# MFO.net
KiCad netlist of a schematic drawn in EAGLE
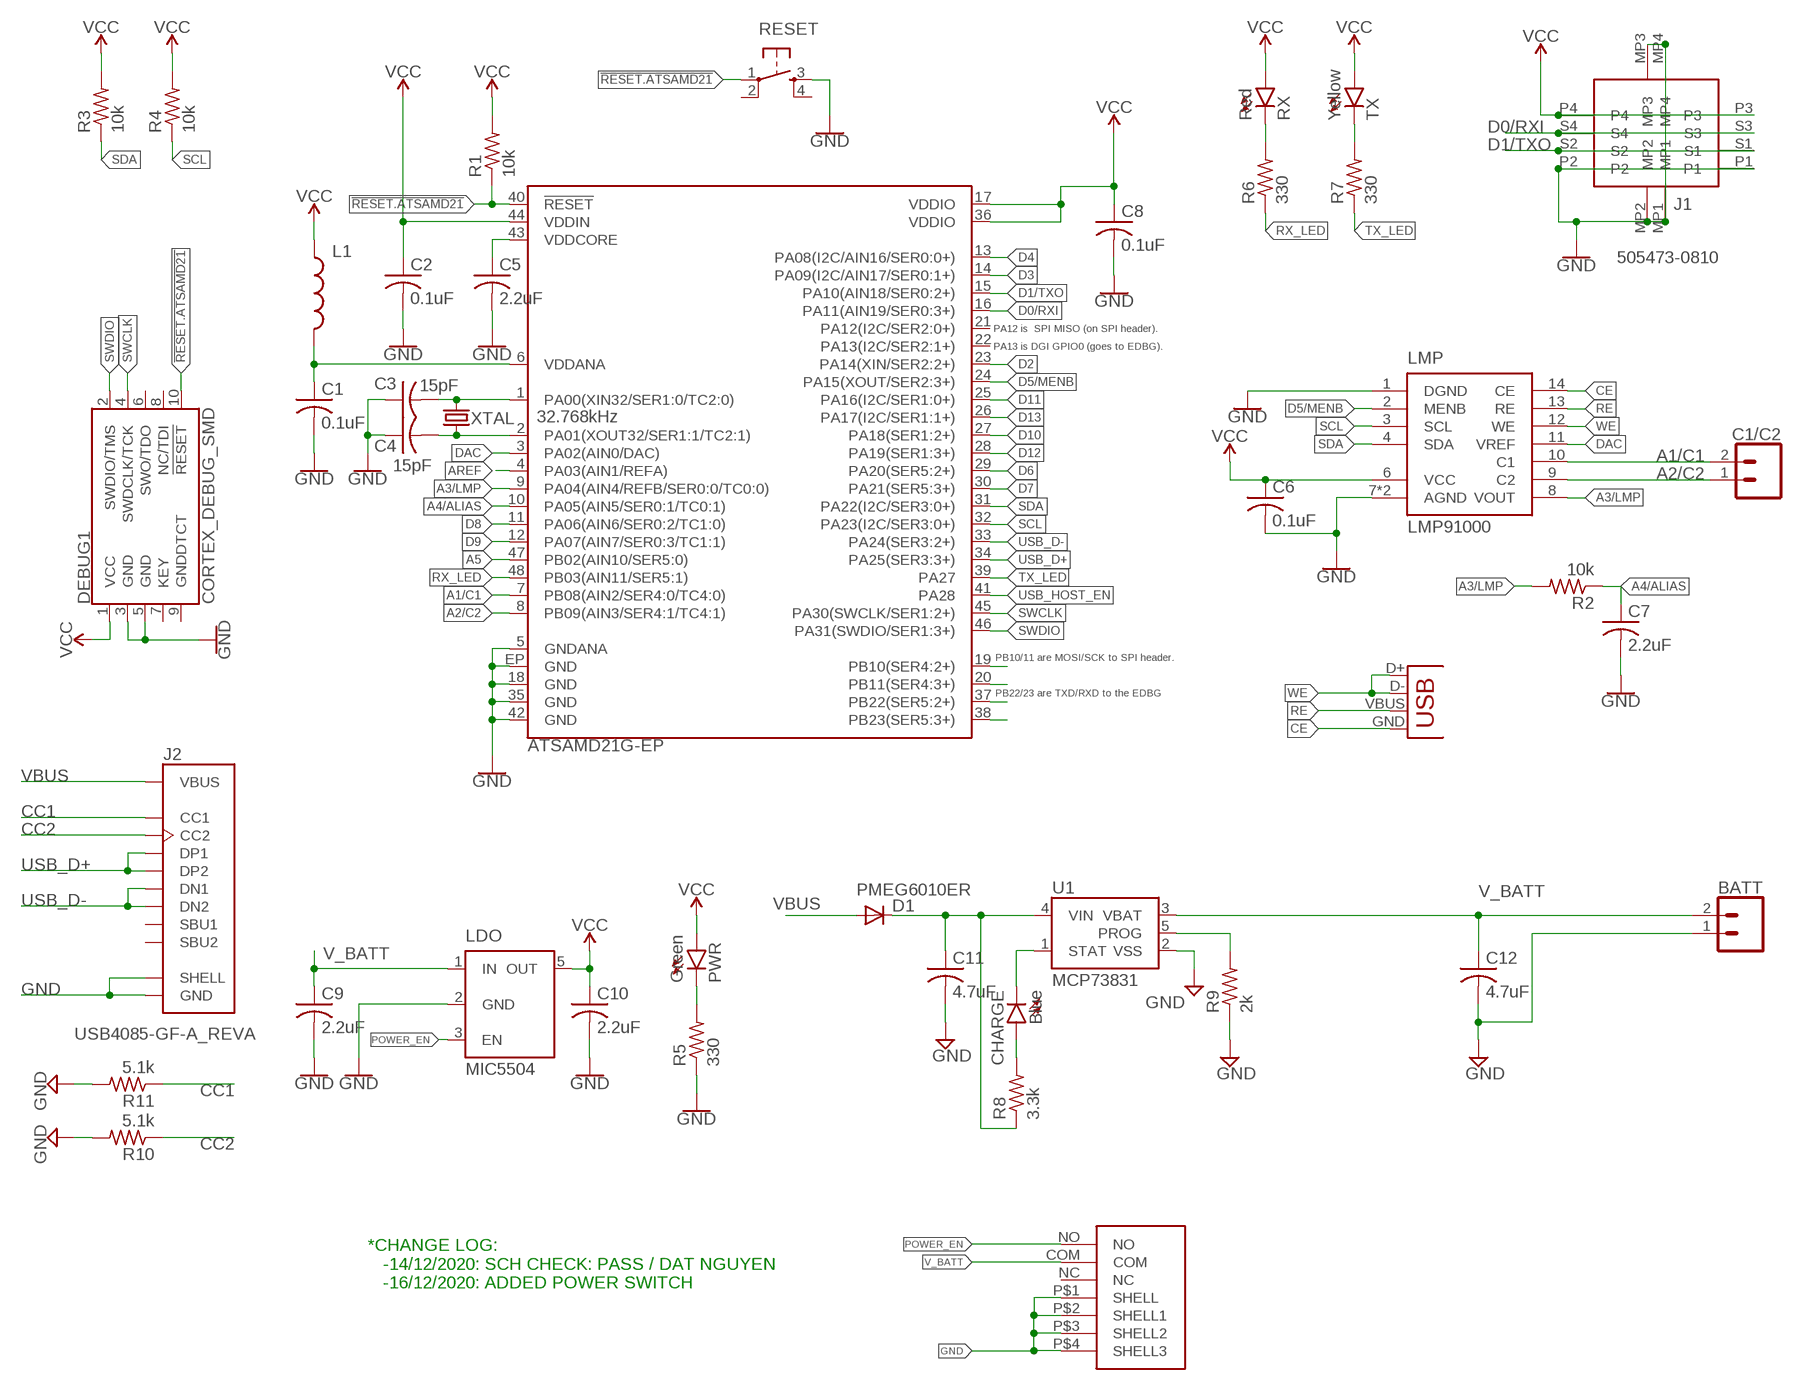
[diagram p0: schematic, sheet 1]

(export (version "E")
  (design (tool "Eeschema 10.0.6"))
  (components
    (comp (ref "ARDUINO")
      (value "ATSAMD21G-EP")
      (footprint "eagle-import:QFN-48")
      (libsource (lib "eagle-import") (part "ATSAMD21G-EP"))
    )
    (comp (ref "BATT")
      (value "CONN_02")
      (footprint "eagle-import:1X02")
      (libsource (lib "eagle-import") (part "CONN_02"))
    )
    (comp (ref "C1")
      (value "0.1uF")
      (footprint "eagle-import:C0603")
      (libsource (lib "eagle-import") (part "C-USC0603"))
    )
    (comp (ref "C1/C2")
      (value "CONN_02")
      (footprint "eagle-import:1X02")
      (libsource (lib "eagle-import") (part "CONN_02"))
    )
    (comp (ref "C2")
      (value "0.1uF")
      (footprint "eagle-import:C0603")
      (libsource (lib "eagle-import") (part "C-USC0603"))
    )
    (comp (ref "C3")
      (value "15pF")
      (footprint "eagle-import:C0603")
      (libsource (lib "eagle-import") (part "C-USC0603"))
    )
    (comp (ref "C4")
      (value "15pF")
      (footprint "eagle-import:C0603")
      (libsource (lib "eagle-import") (part "C-USC0603"))
    )
    (comp (ref "C5")
      (value "2.2uF")
      (footprint "eagle-import:C0603")
      (libsource (lib "eagle-import") (part "C-USC0603"))
    )
    (comp (ref "C6")
      (value "0.1uF")
      (footprint "eagle-import:C0603")
      (libsource (lib "eagle-import") (part "C-USC0603"))
    )
    (comp (ref "C7")
      (value "2.2uF")
      (footprint "eagle-import:C0603")
      (libsource (lib "eagle-import") (part "C-USC0603"))
    )
    (comp (ref "C8")
      (value "0.1uF")
      (footprint "eagle-import:C0603")
      (libsource (lib "eagle-import") (part "C-USC0603"))
    )
    (comp (ref "C9")
      (value "2.2uF")
      (footprint "eagle-import:C0603")
      (libsource (lib "eagle-import") (part "C-USC0603"))
    )
    (comp (ref "C10")
      (value "2.2uF")
      (footprint "eagle-import:C0603")
      (libsource (lib "eagle-import") (part "C-USC0603"))
    )
    (comp (ref "C11")
      (value "4.7uF")
      (footprint "eagle-import:C0603")
      (libsource (lib "eagle-import") (part "C-USC0603"))
    )
    (comp (ref "C12")
      (value "4.7uF")
      (footprint "eagle-import:C0603")
      (libsource (lib "eagle-import") (part "C-USC0603"))
    )
    (comp (ref "CHARGE")
      (value "Blue")
      (footprint "eagle-import:CHIP-LED0805")
      (libsource (lib "eagle-import") (part "LEDCHIP-LED0805"))
    )
    (comp (ref "D1")
      (value "PMEG6010ER")
      (footprint "eagle-import:DIODE_SOD123")
      (libsource (lib "eagle-import") (part "DIODE_DIODE-SOD123"))
    )
    (comp (ref "DEBUG1")
      (value "CORTEX_DEBUG_SMD")
      (footprint "eagle-import:SAMTECH_FTSH-105-01")
      (libsource (lib "eagle-import") (part "CORTEX_DEBUG_SMD"))
    )
    (comp (ref "J1")
      (value "505473-0810")
      (footprint "eagle-import:5054730810")
      (fields (field (name "MOUSER_PART_NUMBER") "538-5054730810"))
      (libsource (lib "eagle-import") (part "505473-0810"))
    )
    (comp (ref "J2")
      (value "USB4085-GF-A_REVA")
      (footprint "eagle-import:GCT_USB4085-GF-A_REVA")
      (fields (field (name "MF") "Global Connector Technology") (field (name "MP") "USB4085-GF-A"))
      (libsource (lib "eagle-import") (part "USB4085-GF-A_REVA"))
    )
    (comp (ref "L1")
      (value "FB - 30Ohm")
      (footprint "eagle-import:L0603")
      (libsource (lib "eagle-import") (part "INDUCTOR0603"))
    )
    (comp (ref "LDO")
      (value "MIC5504")
      (footprint "eagle-import:SOT23-5")
      (libsource (lib "eagle-import") (part "MIC5504"))
    )
    (comp (ref "LMP")
      (value "LMP91000")
      (footprint "eagle-import:WSON-14")
      (libsource (lib "eagle-import") (part "LMP91000"))
    )
    (comp (ref "PWR")
      (value "Green")
      (footprint "eagle-import:CHIP-LED0805")
      (libsource (lib "eagle-import") (part "LEDCHIP-LED0805"))
    )
    (comp (ref "R1")
      (value "10k")
      (footprint "eagle-import:R0603")
      (libsource (lib "eagle-import") (part "R-US_R0603"))
    )
    (comp (ref "R2")
      (value "10k")
      (footprint "eagle-import:R0603")
      (libsource (lib "eagle-import") (part "R-US_R0603"))
    )
    (comp (ref "R3")
      (value "10k")
      (footprint "eagle-import:R0603")
      (libsource (lib "eagle-import") (part "R-US_R0603"))
    )
    (comp (ref "R4")
      (value "10k")
      (footprint "eagle-import:R0603")
      (libsource (lib "eagle-import") (part "R-US_R0603"))
    )
    (comp (ref "R5")
      (value "330")
      (footprint "eagle-import:R0603")
      (libsource (lib "eagle-import") (part "R-US_R0603"))
    )
    (comp (ref "R6")
      (value "330")
      (footprint "eagle-import:R0603")
      (libsource (lib "eagle-import") (part "R-US_R0603"))
    )
    (comp (ref "R7")
      (value "330")
      (footprint "eagle-import:R0603")
      (libsource (lib "eagle-import") (part "R-US_R0603"))
    )
    (comp (ref "R8")
      (value "3.3k")
      (footprint "eagle-import:R0603")
      (libsource (lib "eagle-import") (part "R-US_R0603"))
    )
    (comp (ref "R9")
      (value "2k")
      (footprint "eagle-import:R0603")
      (libsource (lib "eagle-import") (part "R-US_R0603"))
    )
    (comp (ref "R10")
      (value "5.1k")
      (footprint "eagle-import:R0603")
      (libsource (lib "eagle-import") (part "R-US_R0603"))
    )
    (comp (ref "R11")
      (value "5.1k")
      (footprint "eagle-import:R0603")
      (libsource (lib "eagle-import") (part "R-US_R0603"))
    )
    (comp (ref "RESET")
      (value "SPST-PTS830GG140")
      (footprint "eagle-import:BUTTON-GULLWING")
      (libsource (lib "eagle-import") (part "SPST-PTS830GG140"))
    )
    (comp (ref "RX")
      (value "Red")
      (footprint "eagle-import:CHIP-LED0805")
      (libsource (lib "eagle-import") (part "LEDCHIP-LED0805"))
    )
    (comp (ref "TX")
      (value "Yellow")
      (footprint "eagle-import:CHIP-LED0805")
      (libsource (lib "eagle-import") (part "LEDCHIP-LED0805"))
    )
    (comp (ref "U$1")
      (value "MSK-12C02SMD")
      (footprint "eagle-import:MSK-12C02SMD")
      (libsource (lib "eagle-import") (part "MSK-12C02SMD"))
    )
    (comp (ref "U1")
      (value "MCP73831")
      (footprint "eagle-import:SOT23-5")
      (libsource (lib "eagle-import") (part "MCP73831SMD"))
    )
    (comp (ref "X1")
      (value "USB-A-H")
      (footprint "eagle-import:USB-A-H")
      (libsource (lib "eagle-import") (part "USB-A-H"))
    )
    (comp (ref "XTAL")
      (value "32.768kHz")
      (footprint "eagle-import:2-SMD.NOLEAD.1.2MMTO1.0MM")
      (libsource (lib "eagle-import") (part "CRYSTALECS-.327-12.5-1210-TR"))
    )
  )
  (nets
    (net (code "1") (name "/CC1") (class "Default")
      (node (ref "J2") (pin "A5") (pinfunction "CC1_A5") (pintype "bidirectional"))
      (node (ref "R11") (pin "1") (pinfunction "1_1") (pintype "passive"))
    )
    (net (code "2") (name "/CC2") (class "Default")
      (node (ref "J2") (pin "B5") (pinfunction "CC2_B5") (pintype "bidirectional"))
      (node (ref "R10") (pin "1") (pinfunction "1_1") (pintype "passive"))
    )
    (net (code "3") (name "/VBUS") (class "Default")
      (node (ref "D1") (pin "A") (pinfunction "A_A") (pintype "passive"))
      (node (ref "J2") (pin "A4") (pinfunction "VBUS_A4") (pintype "power_in"))
      (node (ref "J2") (pin "A9") (pinfunction "VBUS_A9") (pintype "power_in"))
      (node (ref "J2") (pin "B4") (pinfunction "VBUS_B4") (pintype "power_in"))
      (node (ref "J2") (pin "B9") (pinfunction "VBUS_B9") (pintype "power_in"))
    )
    (net (code "4") (name "/~{RESET.ATSAMD21}") (class "Default")
      (node (ref "ARDUINO") (pin "40") (pinfunction "~{RESET}_40") (pintype "bidirectional"))
      (node (ref "DEBUG1") (pin "10") (pinfunction "~{RESET}_10") (pintype "bidirectional"))
      (node (ref "R1") (pin "1") (pinfunction "1_1") (pintype "passive"))
      (node (ref "RESET") (pin "1") (pinfunction "1_1") (pintype "passive"))
    )
    (net (code "5") (name "A1{slash}C1") (class "Default")
      (node (ref "ARDUINO") (pin "7") (pinfunction "PB08(AIN2/SER4:0/TC4:0)_7") (pintype "bidirectional"))
      (node (ref "C1/C2") (pin "2") (pinfunction "2_2") (pintype "passive"))
      (node (ref "LMP") (pin "10") (pinfunction "C1_10") (pintype "bidirectional"))
    )
    (net (code "6") (name "A2{slash}C2") (class "Default")
      (node (ref "ARDUINO") (pin "8") (pinfunction "PB09(AIN3/SER4:1/TC4:1)_8") (pintype "bidirectional"))
      (node (ref "C1/C2") (pin "1") (pinfunction "1_1") (pintype "passive"))
      (node (ref "LMP") (pin "9") (pinfunction "C2_9") (pintype "bidirectional"))
    )
    (net (code "7") (name "A3{slash}LMP") (class "Default")
      (node (ref "ARDUINO") (pin "9") (pinfunction "PA04(AIN4/REFB/SER0:0/TC0:0)_9") (pintype "bidirectional"))
      (node (ref "LMP") (pin "8") (pinfunction "VOUT_8") (pintype "bidirectional"))
      (node (ref "R2") (pin "2") (pinfunction "2_2") (pintype "passive"))
    )
    (net (code "8") (name "A4{slash}ALIAS") (class "Default")
      (node (ref "ARDUINO") (pin "10") (pinfunction "PA05(AIN5/SER0:1/TC0:1)_10") (pintype "bidirectional"))
      (node (ref "C7") (pin "1") (pinfunction "1_1") (pintype "passive"))
      (node (ref "R2") (pin "1") (pinfunction "1_1") (pintype "passive"))
    )
    (net (code "9") (name "A5") (class "Default")
      (node (ref "ARDUINO") (pin "47") (pinfunction "PB02(AIN10/SER5:0)_47") (pintype "bidirectional"))
    )
    (net (code "10") (name "AREF") (class "Default")
      (node (ref "ARDUINO") (pin "4") (pinfunction "PA03(AIN1/REFA)_4") (pintype "bidirectional"))
    )
    (net (code "11") (name "CE") (class "Default")
      (node (ref "LMP") (pin "14") (pinfunction "CE_14") (pintype "bidirectional"))
      (node (ref "X1") (pin "GND") (pinfunction "GND_GND") (pintype "bidirectional"))
    )
    (net (code "12") (name "D0{slash}RXI") (class "Default")
      (node (ref "ARDUINO") (pin "16") (pinfunction "PA11(AIN19/SER0:3+)_16") (pintype "bidirectional"))
      (node (ref "J1") (pin "S3") (pinfunction "S3_S3") (pintype "bidirectional"))
      (node (ref "J1") (pin "S4") (pinfunction "S4_S4") (pintype "bidirectional"))
    )
    (net (code "13") (name "D1{slash}TXO") (class "Default")
      (node (ref "ARDUINO") (pin "15") (pinfunction "PA10(AIN18/SER0:2+)_15") (pintype "bidirectional"))
      (node (ref "J1") (pin "S1") (pinfunction "S1_S1") (pintype "bidirectional"))
      (node (ref "J1") (pin "S2") (pinfunction "S2_S2") (pintype "bidirectional"))
    )
    (net (code "14") (name "D2") (class "Default")
      (node (ref "ARDUINO") (pin "23") (pinfunction "PA14(XIN/SER2:2+)_23") (pintype "bidirectional"))
    )
    (net (code "15") (name "D3") (class "Default")
      (node (ref "ARDUINO") (pin "14") (pinfunction "PA09(I2C/AIN17/SER0:1+)_14") (pintype "bidirectional"))
    )
    (net (code "16") (name "D4") (class "Default")
      (node (ref "ARDUINO") (pin "13") (pinfunction "PA08(I2C/AIN16/SER0:0+)_13") (pintype "bidirectional"))
    )
    (net (code "17") (name "D5{slash}MENB") (class "Default")
      (node (ref "ARDUINO") (pin "24") (pinfunction "PA15(XOUT/SER2:3+)_24") (pintype "bidirectional"))
      (node (ref "LMP") (pin "2") (pinfunction "MENB_2") (pintype "bidirectional"))
    )
    (net (code "18") (name "D6") (class "Default")
      (node (ref "ARDUINO") (pin "29") (pinfunction "PA20(SER5:2+)_29") (pintype "bidirectional"))
    )
    (net (code "19") (name "D7") (class "Default")
      (node (ref "ARDUINO") (pin "30") (pinfunction "PA21(SER5:3+)_30") (pintype "bidirectional"))
    )
    (net (code "20") (name "D8") (class "Default")
      (node (ref "ARDUINO") (pin "11") (pinfunction "PA06(AIN6/SER0:2/TC1:0)_11") (pintype "bidirectional"))
    )
    (net (code "21") (name "D9") (class "Default")
      (node (ref "ARDUINO") (pin "12") (pinfunction "PA07(AIN7/SER0:3/TC1:1)_12") (pintype "bidirectional"))
    )
    (net (code "22") (name "D10") (class "Default")
      (node (ref "ARDUINO") (pin "27") (pinfunction "PA18(SER1:2+)_27") (pintype "bidirectional"))
    )
    (net (code "23") (name "D11") (class "Default")
      (node (ref "ARDUINO") (pin "25") (pinfunction "PA16(I2C/SER1:0+)_25") (pintype "bidirectional"))
    )
    (net (code "24") (name "D12") (class "Default")
      (node (ref "ARDUINO") (pin "28") (pinfunction "PA19(SER1:3+)_28") (pintype "bidirectional"))
    )
    (net (code "25") (name "D13") (class "Default")
      (node (ref "ARDUINO") (pin "26") (pinfunction "PA17(I2C/SER1:1+)_26") (pintype "bidirectional"))
    )
    (net (code "26") (name "DAC") (class "Default")
      (node (ref "ARDUINO") (pin "3") (pinfunction "PA02(AIN0/DAC)_3") (pintype "bidirectional"))
      (node (ref "LMP") (pin "11") (pinfunction "VREF_11") (pintype "bidirectional"))
    )
    (net (code "27") (name "GND") (class "Default")
      (node (ref "ARDUINO") (pin "18") (pinfunction "GND_18") (pintype "bidirectional"))
      (node (ref "ARDUINO") (pin "35") (pinfunction "GND_35") (pintype "bidirectional"))
      (node (ref "ARDUINO") (pin "42") (pinfunction "GND_42") (pintype "bidirectional"))
      (node (ref "ARDUINO") (pin "5") (pinfunction "GNDANA_5") (pintype "bidirectional"))
      (node (ref "ARDUINO") (pin "EP") (pinfunction "GND_EP") (pintype "bidirectional"))
      (node (ref "BATT") (pin "1") (pinfunction "1_1") (pintype "passive"))
      (node (ref "C1") (pin "2") (pinfunction "2_2") (pintype "passive"))
      (node (ref "C10") (pin "2") (pinfunction "2_2") (pintype "passive"))
      (node (ref "C11") (pin "2") (pinfunction "2_2") (pintype "passive"))
      (node (ref "C12") (pin "2") (pinfunction "2_2") (pintype "passive"))
      (node (ref "C2") (pin "2") (pinfunction "2_2") (pintype "passive"))
      (node (ref "C3") (pin "1") (pinfunction "1_1") (pintype "passive"))
      (node (ref "C4") (pin "1") (pinfunction "1_1") (pintype "passive"))
      (node (ref "C5") (pin "2") (pinfunction "2_2") (pintype "passive"))
      (node (ref "C6") (pin "2") (pinfunction "2_2") (pintype "passive"))
      (node (ref "C7") (pin "2") (pinfunction "2_2") (pintype "passive"))
      (node (ref "C8") (pin "2") (pinfunction "2_2") (pintype "passive"))
      (node (ref "C9") (pin "2") (pinfunction "2_2") (pintype "passive"))
      (node (ref "DEBUG1") (pin "3") (pinfunction "GND_3") (pintype "bidirectional"))
      (node (ref "DEBUG1") (pin "5") (pinfunction "GND_5") (pintype "bidirectional"))
      (node (ref "J1") (pin "MP1") (pinfunction "MP1_MP1") (pintype "bidirectional"))
      (node (ref "J1") (pin "MP2") (pinfunction "MP2_MP2") (pintype "bidirectional"))
      (node (ref "J1") (pin "MP3") (pinfunction "MP3_MP3") (pintype "bidirectional"))
      (node (ref "J1") (pin "MP4") (pinfunction "MP4_MP4") (pintype "bidirectional"))
      (node (ref "J1") (pin "P1") (pinfunction "P1_P1") (pintype "bidirectional"))
      (node (ref "J1") (pin "P2") (pinfunction "P2_P2") (pintype "bidirectional"))
      (node (ref "J2") (pin "A1") (pinfunction "GND_A1") (pintype "passive"))
      (node (ref "J2") (pin "A12") (pinfunction "GND_A12") (pintype "passive"))
      (node (ref "J2") (pin "B1") (pinfunction "GND_B1") (pintype "passive"))
      (node (ref "J2") (pin "B12") (pinfunction "GND_B12") (pintype "passive"))
      (node (ref "J2") (pin "P1") (pinfunction "SHELL_P1") (pintype "passive"))
      (node (ref "J2") (pin "P2") (pinfunction "SHELL_P2") (pintype "passive"))
      (node (ref "J2") (pin "P3") (pinfunction "SHELL_P3") (pintype "passive"))
      (node (ref "J2") (pin "P4") (pinfunction "SHELL_P4") (pintype "passive"))
      (node (ref "LDO") (pin "2") (pinfunction "GND_2") (pintype "bidirectional"))
      (node (ref "LMP") (pin "1") (pinfunction "DGND_1") (pintype "bidirectional"))
      (node (ref "LMP") (pin "7") (pinfunction "AGND_7") (pintype "bidirectional"))
      (node (ref "LMP") (pin "DAP") (pinfunction "AGND_DAP") (pintype "bidirectional"))
      (node (ref "R10") (pin "2") (pinfunction "2_2") (pintype "passive"))
      (node (ref "R11") (pin "2") (pinfunction "2_2") (pintype "passive"))
      (node (ref "R5") (pin "1") (pinfunction "1_1") (pintype "passive"))
      (node (ref "R9") (pin "1") (pinfunction "1_1") (pintype "passive"))
      (node (ref "RESET") (pin "3") (pinfunction "3_3") (pintype "passive"))
      (node (ref "U$1") (pin "P$1") (pinfunction "SHELL_P$1") (pintype "bidirectional"))
      (node (ref "U$1") (pin "P$2") (pinfunction "SHELL1_P$2") (pintype "bidirectional"))
      (node (ref "U$1") (pin "P$3") (pinfunction "SHELL2_P$3") (pintype "bidirectional"))
      (node (ref "U$1") (pin "P$4") (pinfunction "SHELL3_P$4") (pintype "bidirectional"))
      (node (ref "U1") (pin "2") (pinfunction "VSS_2") (pintype "power_in"))
    )
    (net (code "28") (name "Net-(ARDUINO-PA00(XIN32{slash}SER1:0{slash}TC2:0))") (class "Default")
      (node (ref "ARDUINO") (pin "1") (pinfunction "PA00(XIN32/SER1:0/TC2:0)_1") (pintype "bidirectional"))
      (node (ref "C3") (pin "2") (pinfunction "2_2") (pintype "passive"))
      (node (ref "XTAL") (pin "P$2") (pinfunction "2_P$2") (pintype "passive"))
    )
    (net (code "29") (name "Net-(ARDUINO-PA01(XOUT32{slash}SER1:1{slash}TC2:1))") (class "Default")
      (node (ref "ARDUINO") (pin "2") (pinfunction "PA01(XOUT32/SER1:1/TC2:1)_2") (pintype "bidirectional"))
      (node (ref "C4") (pin "2") (pinfunction "2_2") (pintype "passive"))
      (node (ref "XTAL") (pin "P$1") (pinfunction "1_P$1") (pintype "passive"))
    )
    (net (code "30") (name "Net-(ARDUINO-VDDANA)") (class "Default")
      (node (ref "ARDUINO") (pin "6") (pinfunction "VDDANA_6") (pintype "bidirectional"))
      (node (ref "C1") (pin "1") (pinfunction "1_1") (pintype "passive"))
      (node (ref "L1") (pin "2") (pinfunction "2_2") (pintype "passive"))
    )
    (net (code "31") (name "Net-(ARDUINO-VDDCORE)") (class "Default")
      (node (ref "ARDUINO") (pin "43") (pinfunction "VDDCORE_43") (pintype "bidirectional"))
      (node (ref "C5") (pin "1") (pinfunction "1_1") (pintype "passive"))
    )
    (net (code "32") (name "Net-(CHARGE-PadA)") (class "Default")
      (node (ref "CHARGE") (pin "A") (pinfunction "A_A") (pintype "passive"))
      (node (ref "R8") (pin "2") (pinfunction "2_2") (pintype "passive"))
    )
    (net (code "33") (name "Net-(PWR-PadC)") (class "Default")
      (node (ref "PWR") (pin "C") (pinfunction "C_C") (pintype "passive"))
      (node (ref "R5") (pin "2") (pinfunction "2_2") (pintype "passive"))
    )
    (net (code "34") (name "Net-(R6-Pad2)") (class "Default")
      (node (ref "R6") (pin "2") (pinfunction "2_2") (pintype "passive"))
      (node (ref "RX") (pin "C") (pinfunction "C_C") (pintype "passive"))
    )
    (net (code "35") (name "Net-(R7-Pad2)") (class "Default")
      (node (ref "R7") (pin "2") (pinfunction "2_2") (pintype "passive"))
      (node (ref "TX") (pin "C") (pinfunction "C_C") (pintype "passive"))
    )
    (net (code "36") (name "Net-(U1-PROG)") (class "Default")
      (node (ref "R9") (pin "2") (pinfunction "2_2") (pintype "passive"))
      (node (ref "U1") (pin "5") (pinfunction "PROG_5") (pintype "input"))
    )
    (net (code "37") (name "Net-(U1-STAT)") (class "Default")
      (node (ref "CHARGE") (pin "C") (pinfunction "C_C") (pintype "passive"))
      (node (ref "U1") (pin "1") (pinfunction "STAT_1") (pintype "output"))
    )
    (net (code "38") (name "Net-(U1-VIN)") (class "Default")
      (node (ref "C11") (pin "1") (pinfunction "1_1") (pintype "passive"))
      (node (ref "D1") (pin "C") (pinfunction "C_C") (pintype "passive"))
      (node (ref "R8") (pin "1") (pinfunction "1_1") (pintype "passive"))
      (node (ref "U1") (pin "4") (pinfunction "VIN_4") (pintype "power_in"))
    )
    (net (code "39") (name "POWER_EN") (class "Default")
      (node (ref "LDO") (pin "3") (pinfunction "EN_3") (pintype "bidirectional"))
      (node (ref "U$1") (pin "NO") (pinfunction "NO_NO") (pintype "bidirectional"))
    )
    (net (code "40") (name "RE") (class "Default")
      (node (ref "LMP") (pin "13") (pinfunction "RE_13") (pintype "bidirectional"))
      (node (ref "X1") (pin "VBUS") (pinfunction "VBUS_VBUS") (pintype "bidirectional"))
    )
    (net (code "41") (name "RX_LED") (class "Default")
      (node (ref "ARDUINO") (pin "48") (pinfunction "PB03(AIN11/SER5:1)_48") (pintype "bidirectional"))
      (node (ref "R6") (pin "1") (pinfunction "1_1") (pintype "passive"))
    )
    (net (code "42") (name "SCL") (class "Default")
      (node (ref "ARDUINO") (pin "32") (pinfunction "PA23(I2C/SER3:0+)_32") (pintype "bidirectional"))
      (node (ref "LMP") (pin "3") (pinfunction "SCL_3") (pintype "bidirectional"))
      (node (ref "R4") (pin "1") (pinfunction "1_1") (pintype "passive"))
    )
    (net (code "43") (name "SDA") (class "Default")
      (node (ref "ARDUINO") (pin "31") (pinfunction "PA22(I2C/SER3:0+)_31") (pintype "bidirectional"))
      (node (ref "LMP") (pin "4") (pinfunction "SDA_4") (pintype "bidirectional"))
      (node (ref "R3") (pin "1") (pinfunction "1_1") (pintype "passive"))
    )
    (net (code "44") (name "SWCLK") (class "Default")
      (node (ref "ARDUINO") (pin "45") (pinfunction "PA30(SWCLK/SER1:2+)_45") (pintype "bidirectional"))
      (node (ref "DEBUG1") (pin "4") (pinfunction "SWDCLK/TCK_4") (pintype "bidirectional"))
    )
    (net (code "45") (name "SWDIO") (class "Default")
      (node (ref "ARDUINO") (pin "46") (pinfunction "PA31(SWDIO/SER1:3+)_46") (pintype "bidirectional"))
      (node (ref "DEBUG1") (pin "2") (pinfunction "SWDIO/TMS_2") (pintype "bidirectional"))
    )
    (net (code "46") (name "TX_LED") (class "Default")
      (node (ref "ARDUINO") (pin "39") (pinfunction "PA27_39") (pintype "bidirectional"))
      (node (ref "R7") (pin "1") (pinfunction "1_1") (pintype "passive"))
    )
    (net (code "47") (name "USB_D+") (class "Default")
      (node (ref "ARDUINO") (pin "34") (pinfunction "PA25(SER3:3+)_34") (pintype "bidirectional"))
      (node (ref "J2") (pin "A6") (pinfunction "DP1_A6") (pintype "bidirectional"))
      (node (ref "J2") (pin "B6") (pinfunction "DP2_B6") (pintype "bidirectional"))
    )
    (net (code "48") (name "USB_D-") (class "Default")
      (node (ref "ARDUINO") (pin "33") (pinfunction "PA24(SER3:2+)_33") (pintype "bidirectional"))
      (node (ref "J2") (pin "A7") (pinfunction "DN1_A7") (pintype "bidirectional"))
      (node (ref "J2") (pin "B7") (pinfunction "DN2_B7") (pintype "bidirectional"))
    )
    (net (code "49") (name "USB_HOST_EN") (class "Default")
      (node (ref "ARDUINO") (pin "41") (pinfunction "PA28_41") (pintype "bidirectional"))
    )
    (net (code "50") (name "VCC") (class "Default")
      (node (ref "ARDUINO") (pin "17") (pinfunction "VDDIO_17") (pintype "bidirectional"))
      (node (ref "ARDUINO") (pin "36") (pinfunction "VDDIO_36") (pintype "bidirectional"))
      (node (ref "ARDUINO") (pin "44") (pinfunction "VDDIN_44") (pintype "bidirectional"))
      (node (ref "C10") (pin "1") (pinfunction "1_1") (pintype "passive"))
      (node (ref "C2") (pin "1") (pinfunction "1_1") (pintype "passive"))
      (node (ref "C6") (pin "1") (pinfunction "1_1") (pintype "passive"))
      (node (ref "C8") (pin "1") (pinfunction "1_1") (pintype "passive"))
      (node (ref "DEBUG1") (pin "1") (pinfunction "VCC_1") (pintype "bidirectional"))
      (node (ref "J1") (pin "P3") (pinfunction "P3_P3") (pintype "bidirectional"))
      (node (ref "J1") (pin "P4") (pinfunction "P4_P4") (pintype "bidirectional"))
      (node (ref "L1") (pin "1") (pinfunction "1_1") (pintype "passive"))
      (node (ref "LDO") (pin "5") (pinfunction "OUT_5") (pintype "bidirectional"))
      (node (ref "LMP") (pin "6") (pinfunction "VCC_6") (pintype "bidirectional"))
      (node (ref "PWR") (pin "A") (pinfunction "A_A") (pintype "passive"))
      (node (ref "R1") (pin "2") (pinfunction "2_2") (pintype "passive"))
      (node (ref "R3") (pin "2") (pinfunction "2_2") (pintype "passive"))
      (node (ref "R4") (pin "2") (pinfunction "2_2") (pintype "passive"))
      (node (ref "RX") (pin "A") (pinfunction "A_A") (pintype "passive"))
      (node (ref "TX") (pin "A") (pinfunction "A_A") (pintype "passive"))
    )
    (net (code "51") (name "V_BATT") (class "Default")
      (node (ref "BATT") (pin "2") (pinfunction "2_2") (pintype "passive"))
      (node (ref "C12") (pin "1") (pinfunction "1_1") (pintype "passive"))
      (node (ref "C9") (pin "1") (pinfunction "1_1") (pintype "passive"))
      (node (ref "LDO") (pin "1") (pinfunction "IN_1") (pintype "bidirectional"))
      (node (ref "U$1") (pin "COM") (pinfunction "COM_COM") (pintype "bidirectional"))
      (node (ref "U1") (pin "3") (pinfunction "VBAT_3") (pintype "power_in"))
    )
    (net (code "52") (name "WE") (class "Default")
      (node (ref "LMP") (pin "12") (pinfunction "WE_12") (pintype "bidirectional"))
      (node (ref "X1") (pin "D+") (pinfunction "D+_D+") (pintype "bidirectional"))
      (node (ref "X1") (pin "D-") (pinfunction "D-_D-") (pintype "bidirectional"))
    )
    (net (code "53") (name "unconnected-(ARDUINO-PA12(I2C{slash}SER2:0+)-Pad21)") (class "Default")
      (node (ref "ARDUINO") (pin "21") (pinfunction "PA12(I2C/SER2:0+)_21") (pintype "bidirectional"))
    )
    (net (code "54") (name "unconnected-(ARDUINO-PA13(I2C{slash}SER2:1+)-Pad22)") (class "Default")
      (node (ref "ARDUINO") (pin "22") (pinfunction "PA13(I2C/SER2:1+)_22") (pintype "bidirectional"))
    )
    (net (code "55") (name "unconnected-(ARDUINO-PB10(SER4:2+)-Pad19)") (class "Default")
      (node (ref "ARDUINO") (pin "19") (pinfunction "PB10(SER4:2+)_19") (pintype "bidirectional"))
    )
    (net (code "56") (name "unconnected-(ARDUINO-PB11(SER4:3+)-Pad20)") (class "Default")
      (node (ref "ARDUINO") (pin "20") (pinfunction "PB11(SER4:3+)_20") (pintype "bidirectional"))
    )
    (net (code "57") (name "unconnected-(ARDUINO-PB22(SER5:2+)-Pad37)") (class "Default")
      (node (ref "ARDUINO") (pin "37") (pinfunction "PB22(SER5:2+)_37") (pintype "bidirectional"))
    )
    (net (code "58") (name "unconnected-(ARDUINO-PB23(SER5:3+)-Pad38)") (class "Default")
      (node (ref "ARDUINO") (pin "38") (pinfunction "PB23(SER5:3+)_38") (pintype "bidirectional"))
    )
    (net (code "59") (name "unconnected-(DEBUG1-GNDDTCT-Pad9)") (class "Default")
      (node (ref "DEBUG1") (pin "9") (pinfunction "GNDDTCT_9") (pintype "bidirectional"))
    )
    (net (code "60") (name "unconnected-(DEBUG1-KEY-Pad7)") (class "Default")
      (node (ref "DEBUG1") (pin "7") (pinfunction "KEY_7") (pintype "bidirectional"))
    )
    (net (code "61") (name "unconnected-(DEBUG1-NC{slash}TDI-Pad8)") (class "Default")
      (node (ref "DEBUG1") (pin "8") (pinfunction "NC/TDI_8") (pintype "bidirectional"))
    )
    (net (code "62") (name "unconnected-(DEBUG1-SWO{slash}TDO-Pad6)") (class "Default")
      (node (ref "DEBUG1") (pin "6") (pinfunction "SWO/TDO_6") (pintype "bidirectional"))
    )
    (net (code "63") (name "unconnected-(J2-SBU1-PadA8)") (class "Default")
      (node (ref "J2") (pin "A8") (pinfunction "SBU1_A8") (pintype "bidirectional"))
    )
    (net (code "64") (name "unconnected-(J2-SBU2-PadB8)") (class "Default")
      (node (ref "J2") (pin "B8") (pinfunction "SBU2_B8") (pintype "bidirectional"))
    )
    (net (code "65") (name "unconnected-(RESET-Pad2)") (class "Default")
      (node (ref "RESET") (pin "2") (pinfunction "2_2") (pintype "passive"))
    )
    (net (code "66") (name "unconnected-(RESET-Pad4)") (class "Default")
      (node (ref "RESET") (pin "4") (pinfunction "4_4") (pintype "passive"))
    )
    (net (code "67") (name "unconnected-(U$1-PadNC)") (class "Default")
      (node (ref "U$1") (pin "NC") (pinfunction "NC_NC") (pintype "bidirectional"))
    )
  )
)
